# Crystal.net
KiCad netlist of a schematic drawn in Altium Designer
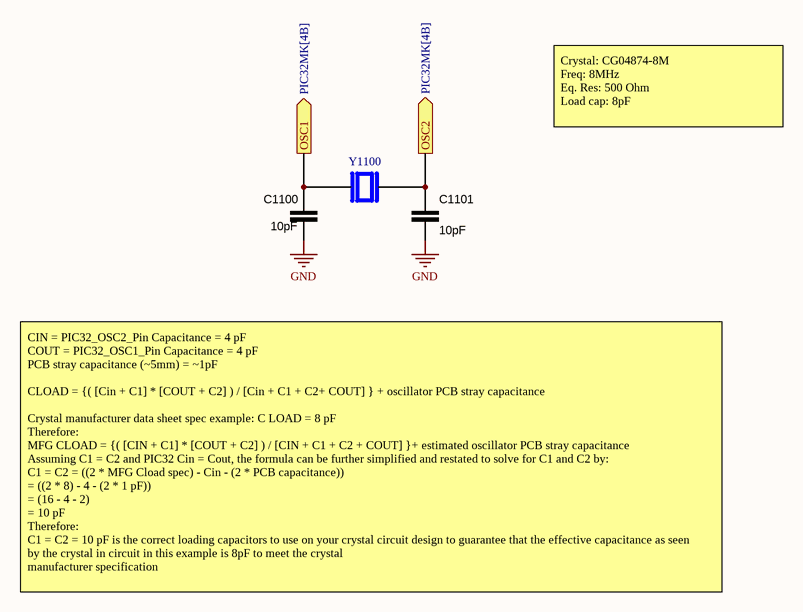
[diagram p0: Crystal.SchDoc]

(export (version "E")
  (design (tool "Eeschema 10.0.6"))
  (components
    (comp (ref "C1100")
      (value "10pF")
      (footprint "CAP_0603")
      (description "CAP CER 10pF 0603 25V X7R")
      (libsource (lib "CapacitorsIntegrated") (part "C000007"))
    )
    (comp (ref "C1101")
      (value "10pF")
      (footprint "CAP_0603")
      (description "CAP CER 10pF 0603 25V X7R")
      (libsource (lib "CapacitorsIntegrated") (part "C000007"))
    )
    (comp (ref "Y1100")
      (value "CG04874-8M")
      (footprint "XTALDFN320X250X100-2N")
      (fields (field (name "MF") "{'manufacturer': u'NDK America, Inc.'}"))
      (libsource (lib "SnapEDA_Library2") (part "CG04874-8M"))
    )
  )
  (nets
    (net (code "1") (name "/OSC1") (class "Default")
      (node (ref "C1100") (pin "1") (pinfunction "1_1") (pintype "passive"))
      (node (ref "Y1100") (pin "1") (pinfunction "1_1") (pintype "passive"))
    )
    (net (code "2") (name "/OSC2") (class "Default")
      (node (ref "C1101") (pin "1") (pinfunction "1_1") (pintype "passive"))
      (node (ref "Y1100") (pin "2") (pinfunction "2_2") (pintype "passive"))
    )
    (net (code "3") (name "GND") (class "Default")
      (node (ref "C1100") (pin "2") (pinfunction "2_2") (pintype "passive"))
      (node (ref "C1101") (pin "2") (pinfunction "2_2") (pintype "passive"))
    )
  )
)
